# ADC.net
KiCad netlist of a schematic drawn in Altium Designer
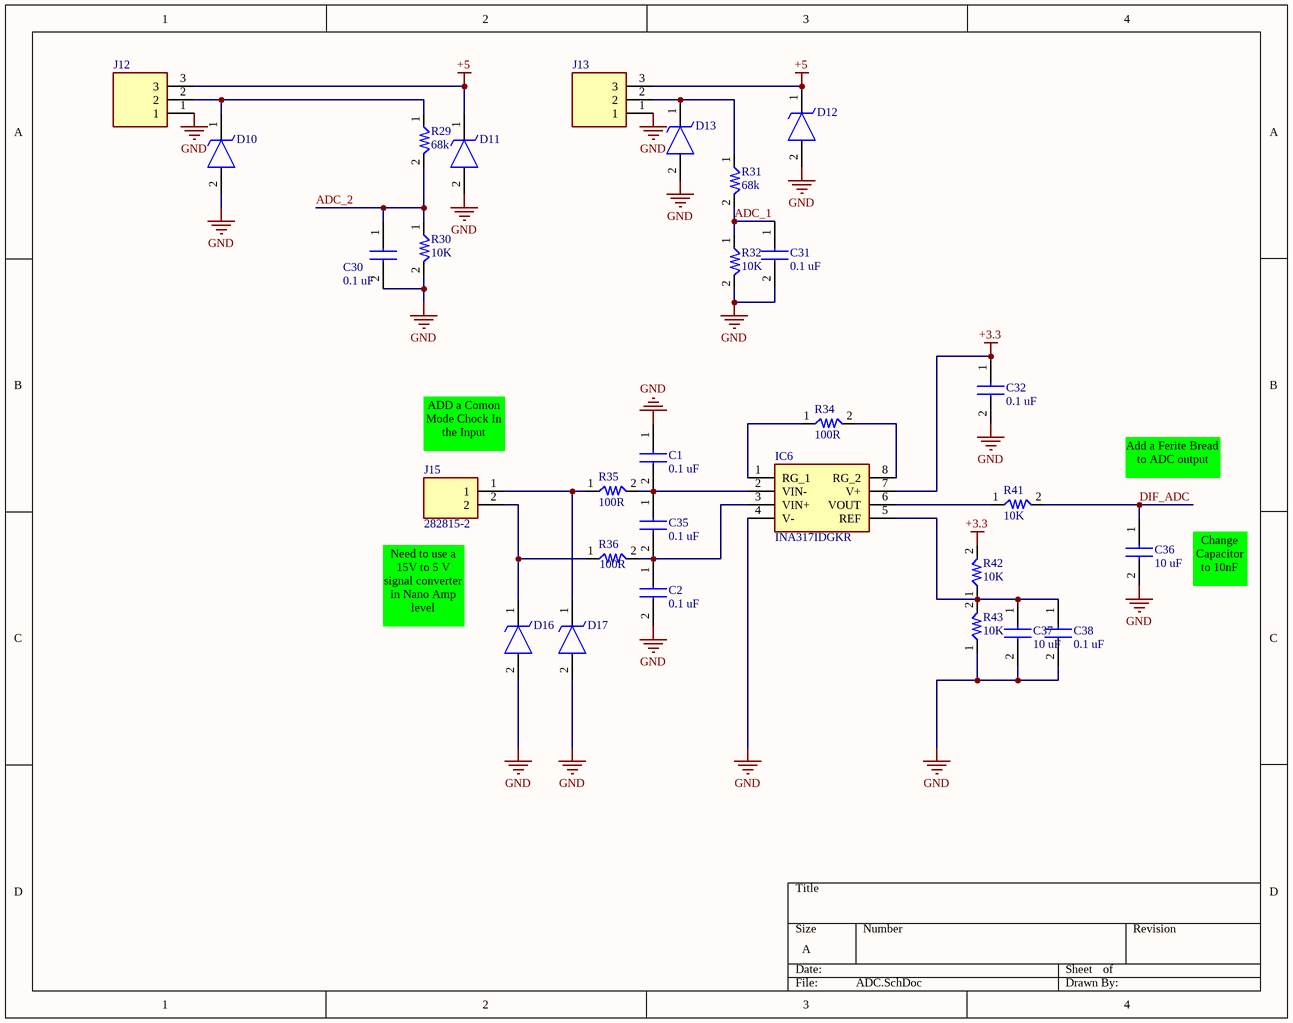
[diagram p0: ADC.SchDoc]

(export (version "E")
  (design (tool "Eeschema 10.0.6"))
  (components
    (comp (ref "C1")
      (value "0.1 uF")
      (footprint "CAP0603")
      (description "Capacitor")
      (fields
        (field (name "MANUFACTURER_PART_NUMBER") "CC0603KRX7R9BB104")
        (field (name "MOUSER PART NUMBER") "603-CC603KRX7R9BB104")
      )
      (libsource (lib "Valve_Controller_Lib") (part "CC0603KRX7R9BB104"))
    )
    (comp (ref "C2")
      (value "0.1 uF")
      (footprint "CAP0603")
      (description "Capacitor")
      (fields
        (field (name "MANUFACTURER_PART_NUMBER") "CC0603KRX7R9BB104")
        (field (name "MOUSER PART NUMBER") "603-CC603KRX7R9BB104")
      )
      (libsource (lib "Valve_Controller_Lib") (part "CC0603KRX7R9BB104"))
    )
    (comp (ref "C30")
      (value "0.1 uF")
      (footprint "CAP0603")
      (description "Capacitor")
      (fields
        (field (name "MANUFACTURER_PART_NUMBER") "CC0603KRX7R9BB104")
        (field (name "MOUSER PART NUMBER") "603-CC603KRX7R9BB104")
      )
      (libsource (lib "Valve_Controller_Lib") (part "CC0603KRX7R9BB104"))
    )
    (comp (ref "C31")
      (value "0.1 uF")
      (footprint "CAP0603")
      (description "Capacitor")
      (fields
        (field (name "MANUFACTURER_PART_NUMBER") "CC0603KRX7R9BB104")
        (field (name "MOUSER PART NUMBER") "603-CC603KRX7R9BB104")
      )
      (libsource (lib "Valve_Controller_Lib") (part "CC0603KRX7R9BB104"))
    )
    (comp (ref "C32")
      (value "0.1 uF")
      (footprint "CAP0603")
      (description "Capacitor")
      (fields
        (field (name "MANUFACTURER_PART_NUMBER") "CC0603KRX7R9BB104")
        (field (name "MOUSER PART NUMBER") "603-CC603KRX7R9BB104")
      )
      (libsource (lib "Valve_Controller_Lib") (part "CC0603KRX7R9BB104"))
    )
    (comp (ref "C35")
      (value "0.1 uF")
      (footprint "CAP0603")
      (description "Capacitor")
      (fields
        (field (name "MANUFACTURER_PART_NUMBER") "CC0603KRX7R9BB104")
        (field (name "MOUSER PART NUMBER") "603-CC603KRX7R9BB104")
      )
      (libsource (lib "Valve_Controller_Lib") (part "CC0603KRX7R9BB104"))
    )
    (comp (ref "C36")
      (value "10 uF")
      (footprint "CAP0603")
      (description "Capacitor")
      (fields
        (field (name "MANUFACTURER_PART_NUMBER") "CC0603KRX7R9BB104")
        (field (name "MOUSER PART NUMBER") "603-CC603KRX7R9BB104")
      )
      (libsource (lib "Valve_Controller_Lib") (part "CC0603KRX7R9BB104"))
    )
    (comp (ref "C37")
      (value "10 uF")
      (footprint "CAP0603")
      (description "Capacitor")
      (fields
        (field (name "MANUFACTURER_PART_NUMBER") "CC0603KRX7R9BB104")
        (field (name "MOUSER PART NUMBER") "603-CC603KRX7R9BB104")
      )
      (libsource (lib "Valve_Controller_Lib") (part "CC0603KRX7R9BB104"))
    )
    (comp (ref "C38")
      (value "0.1 uF")
      (footprint "CAP0603")
      (description "Capacitor")
      (fields
        (field (name "MANUFACTURER_PART_NUMBER") "CC0603KRX7R9BB104")
        (field (name "MOUSER PART NUMBER") "603-CC603KRX7R9BB104")
      )
      (libsource (lib "Valve_Controller_Lib") (part "CC0603KRX7R9BB104"))
    )
    (comp (ref "D10")
      (value "SMBJ5.0A")
      (footprint "SamacSys:SMBJ12A")
      (description "TVS Diode (Uni-directional)")
      (libsource (lib "*") (part "SMBJ5.0A"))
    )
    (comp (ref "D11")
      (value "SMBJ5.0A")
      (footprint "SamacSys:SMBJ12A")
      (description "TVS Diode (Uni-directional)")
      (libsource (lib "*") (part "SMBJ5.0A"))
    )
    (comp (ref "D12")
      (value "SMBJ5.0A")
      (footprint "SamacSys:SMBJ12A")
      (description "TVS Diode (Uni-directional)")
      (libsource (lib "*") (part "SMBJ5.0A"))
    )
    (comp (ref "D13")
      (value "SMBJ5.0A")
      (footprint "SamacSys:SMBJ12A")
      (description "TVS Diode (Uni-directional)")
      (libsource (lib "*") (part "SMBJ5.0A"))
    )
    (comp (ref "D16")
      (value "SMBJ5.0A")
      (footprint "SamacSys:SMBJ12A")
      (description "TVS Diode (Uni-directional)")
      (libsource (lib "*") (part "SMBJ5.0A"))
    )
    (comp (ref "D17")
      (value "SMBJ5.0A")
      (footprint "SamacSys:SMBJ12A")
      (description "TVS Diode (Uni-directional)")
      (libsource (lib "*") (part "SMBJ5.0A"))
    )
    (comp (ref "IC6")
      (value "INA317IDGKR")
      (footprint "SamacSys:SOP65P490X110-8N")
      (description "Integrated Circuit")
      (fields (field (name "MOUSER PART NUMBER") "595-INA317IDGKR"))
      (libsource (lib "*") (part "INA317IDGKR"))
    )
    (comp (ref "J12")
      (value "282815-3")
      (footprint "SamacSys:2828153")
      (description "Connector")
      (fields (field (name "MOUSER PART NUMBER") "571-282815-3"))
      (libsource (lib "*") (part "282815-3"))
    )
    (comp (ref "J13")
      (value "282815-3")
      (footprint "SamacSys:2828153")
      (description "Connector")
      (fields (field (name "MOUSER PART NUMBER") "571-282815-3"))
      (libsource (lib "*") (part "282815-3"))
    )
    (comp (ref "J15")
      (value "282815-2")
      (footprint "SamacSys:SHDRRA2W102P0X508_1X2_1016X1200X850P")
      (description "Connector")
      (fields (field (name "MOUSER PART NUMBER") "571-282815-2"))
      (libsource (lib "*") (part "282815-2"))
    )
    (comp (ref "R29")
      (value "68k")
      (footprint "RES0603")
      (description "Resistor")
      (fields (field (name "MANUFACTURER_PART_NUMBER") "0603WAF1001T5E"))
      (libsource (lib "Valve_Controller_Lib") (part "RES"))
    )
    (comp (ref "R30")
      (value "10K")
      (footprint "RES0603")
      (description "Resistor")
      (fields (field (name "MANUFACTURER_PART_NUMBER") "0603WAF1001T5E"))
      (libsource (lib "Valve_Controller_Lib") (part "RES"))
    )
    (comp (ref "R31")
      (value "68k")
      (footprint "RES0603")
      (description "Resistor")
      (fields (field (name "MANUFACTURER_PART_NUMBER") "0603WAF1001T5E"))
      (libsource (lib "Valve_Controller_Lib") (part "RES"))
    )
    (comp (ref "R32")
      (value "10K")
      (footprint "RES0603")
      (description "Resistor")
      (fields (field (name "MANUFACTURER_PART_NUMBER") "0603WAF1001T5E"))
      (libsource (lib "Valve_Controller_Lib") (part "RES"))
    )
    (comp (ref "R34")
      (value "100R")
      (footprint "RES0603")
      (description "Resistor")
      (fields (field (name "MANUFACTURER_PART_NUMBER") "0603WAF1001T5E"))
      (libsource (lib "Valve_Controller_Lib") (part "RES"))
    )
    (comp (ref "R35")
      (value "100R")
      (footprint "RES0603")
      (description "Resistor")
      (fields (field (name "MANUFACTURER_PART_NUMBER") "0603WAF1001T5E"))
      (libsource (lib "Valve_Controller_Lib") (part "RES"))
    )
    (comp (ref "R36")
      (value "100R")
      (footprint "RES0603")
      (description "Resistor")
      (fields (field (name "MANUFACTURER_PART_NUMBER") "0603WAF1001T5E"))
      (libsource (lib "Valve_Controller_Lib") (part "RES"))
    )
    (comp (ref "R41")
      (value "10K")
      (footprint "RES0603")
      (description "Resistor")
      (fields (field (name "MANUFACTURER_PART_NUMBER") "0603WAF1001T5E"))
      (libsource (lib "Valve_Controller_Lib") (part "RES"))
    )
    (comp (ref "R42")
      (value "10K")
      (footprint "RES0603")
      (description "Resistor")
      (fields (field (name "MANUFACTURER_PART_NUMBER") "0603WAF1001T5E"))
      (libsource (lib "Valve_Controller_Lib") (part "RES"))
    )
    (comp (ref "R43")
      (value "10K")
      (footprint "RES0603")
      (description "Resistor")
      (fields (field (name "MANUFACTURER_PART_NUMBER") "0603WAF1001T5E"))
      (libsource (lib "Valve_Controller_Lib") (part "RES"))
    )
  )
  (nets
    (net (code "1") (name "+3.3") (class "Default")
      (node (ref "C32") (pin "1") (pinfunction "1_1") (pintype "passive"))
      (node (ref "IC6") (pin "7") (pinfunction "V+_7") (pintype "passive"))
      (node (ref "R42") (pin "2") (pinfunction "2_2") (pintype "passive"))
    )
    (net (code "2") (name "+5") (class "Default")
      (node (ref "D11") (pin "1") (pinfunction "K_1") (pintype "passive"))
      (node (ref "D12") (pin "1") (pinfunction "K_1") (pintype "passive"))
      (node (ref "J12") (pin "3") (pinfunction "3_3") (pintype "passive"))
      (node (ref "J13") (pin "3") (pinfunction "3_3") (pintype "passive"))
    )
    (net (code "3") (name "/ADC_1") (class "Default")
      (node (ref "C31") (pin "1") (pinfunction "1_1") (pintype "passive"))
      (node (ref "R31") (pin "2") (pinfunction "2_2") (pintype "passive"))
      (node (ref "R32") (pin "1") (pinfunction "1_1") (pintype "passive"))
    )
    (net (code "4") (name "/ADC_2") (class "Default")
      (node (ref "C30") (pin "1") (pinfunction "1_1") (pintype "passive"))
      (node (ref "R29") (pin "2") (pinfunction "2_2") (pintype "passive"))
      (node (ref "R30") (pin "1") (pinfunction "1_1") (pintype "passive"))
    )
    (net (code "5") (name "/DIF_ADC") (class "Default")
      (node (ref "C36") (pin "1") (pinfunction "1_1") (pintype "passive"))
      (node (ref "R41") (pin "2") (pinfunction "2_2") (pintype "passive"))
    )
    (net (code "6") (name "GND") (class "Default")
      (node (ref "C1") (pin "1") (pinfunction "1_1") (pintype "passive"))
      (node (ref "C2") (pin "2") (pinfunction "2_2") (pintype "passive"))
      (node (ref "C30") (pin "2") (pinfunction "2_2") (pintype "passive"))
      (node (ref "C31") (pin "2") (pinfunction "2_2") (pintype "passive"))
      (node (ref "C32") (pin "2") (pinfunction "2_2") (pintype "passive"))
      (node (ref "C36") (pin "2") (pinfunction "2_2") (pintype "passive"))
      (node (ref "C37") (pin "2") (pinfunction "2_2") (pintype "passive"))
      (node (ref "C38") (pin "2") (pinfunction "2_2") (pintype "passive"))
      (node (ref "D10") (pin "2") (pinfunction "A_2") (pintype "passive"))
      (node (ref "D11") (pin "2") (pinfunction "A_2") (pintype "passive"))
      (node (ref "D12") (pin "2") (pinfunction "A_2") (pintype "passive"))
      (node (ref "D13") (pin "2") (pinfunction "A_2") (pintype "passive"))
      (node (ref "D16") (pin "2") (pinfunction "A_2") (pintype "passive"))
      (node (ref "D17") (pin "2") (pinfunction "A_2") (pintype "passive"))
      (node (ref "IC6") (pin "4") (pinfunction "V-_4") (pintype "passive"))
      (node (ref "J12") (pin "1") (pinfunction "1_1") (pintype "passive"))
      (node (ref "J13") (pin "1") (pinfunction "1_1") (pintype "passive"))
      (node (ref "R30") (pin "2") (pinfunction "2_2") (pintype "passive"))
      (node (ref "R32") (pin "2") (pinfunction "2_2") (pintype "passive"))
      (node (ref "R43") (pin "1") (pinfunction "1_1") (pintype "passive"))
    )
    (net (code "7") (name "Net-(D10-K)") (class "Default")
      (node (ref "D10") (pin "1") (pinfunction "K_1") (pintype "passive"))
      (node (ref "J12") (pin "2") (pinfunction "2_2") (pintype "passive"))
      (node (ref "R29") (pin "1") (pinfunction "1_1") (pintype "passive"))
    )
    (net (code "8") (name "Net-(D13-K)") (class "Default")
      (node (ref "D13") (pin "1") (pinfunction "K_1") (pintype "passive"))
      (node (ref "J13") (pin "2") (pinfunction "2_2") (pintype "passive"))
      (node (ref "R31") (pin "1") (pinfunction "1_1") (pintype "passive"))
    )
    (net (code "9") (name "Net-(D16-K)") (class "Default")
      (node (ref "D16") (pin "1") (pinfunction "K_1") (pintype "passive"))
      (node (ref "J15") (pin "2") (pinfunction "2_2") (pintype "passive"))
      (node (ref "R36") (pin "1") (pinfunction "1_1") (pintype "passive"))
    )
    (net (code "10") (name "Net-(D17-K)") (class "Default")
      (node (ref "D17") (pin "1") (pinfunction "K_1") (pintype "passive"))
      (node (ref "J15") (pin "1") (pinfunction "1_1") (pintype "passive"))
      (node (ref "R35") (pin "1") (pinfunction "1_1") (pintype "passive"))
    )
    (net (code "11") (name "Net-(IC6-REF)") (class "Default")
      (node (ref "C37") (pin "1") (pinfunction "1_1") (pintype "passive"))
      (node (ref "C38") (pin "1") (pinfunction "1_1") (pintype "passive"))
      (node (ref "IC6") (pin "5") (pinfunction "REF_5") (pintype "passive"))
      (node (ref "R42") (pin "1") (pinfunction "1_1") (pintype "passive"))
      (node (ref "R43") (pin "2") (pinfunction "2_2") (pintype "passive"))
    )
    (net (code "12") (name "Net-(IC6-RG_1)") (class "Default")
      (node (ref "IC6") (pin "1") (pinfunction "RG_1_1") (pintype "passive"))
      (node (ref "R34") (pin "1") (pinfunction "1_1") (pintype "passive"))
    )
    (net (code "13") (name "Net-(IC6-RG_2)") (class "Default")
      (node (ref "IC6") (pin "8") (pinfunction "RG_2_8") (pintype "passive"))
      (node (ref "R34") (pin "2") (pinfunction "2_2") (pintype "passive"))
    )
    (net (code "14") (name "Net-(IC6-VIN+)") (class "Default")
      (node (ref "C2") (pin "1") (pinfunction "1_1") (pintype "passive"))
      (node (ref "C35") (pin "2") (pinfunction "2_2") (pintype "passive"))
      (node (ref "IC6") (pin "3") (pinfunction "VIN+_3") (pintype "passive"))
      (node (ref "R36") (pin "2") (pinfunction "2_2") (pintype "passive"))
    )
    (net (code "15") (name "Net-(IC6-VIN-)") (class "Default")
      (node (ref "C1") (pin "2") (pinfunction "2_2") (pintype "passive"))
      (node (ref "C35") (pin "1") (pinfunction "1_1") (pintype "passive"))
      (node (ref "IC6") (pin "2") (pinfunction "VIN-_2") (pintype "passive"))
      (node (ref "R35") (pin "2") (pinfunction "2_2") (pintype "passive"))
    )
    (net (code "16") (name "Net-(IC6-VOUT)") (class "Default")
      (node (ref "IC6") (pin "6") (pinfunction "VOUT_6") (pintype "passive"))
      (node (ref "R41") (pin "1") (pinfunction "1_1") (pintype "passive"))
    )
  )
)
